# HMC5883L_Breakout-v14.net
KiCad netlist of a schematic drawn in EAGLE
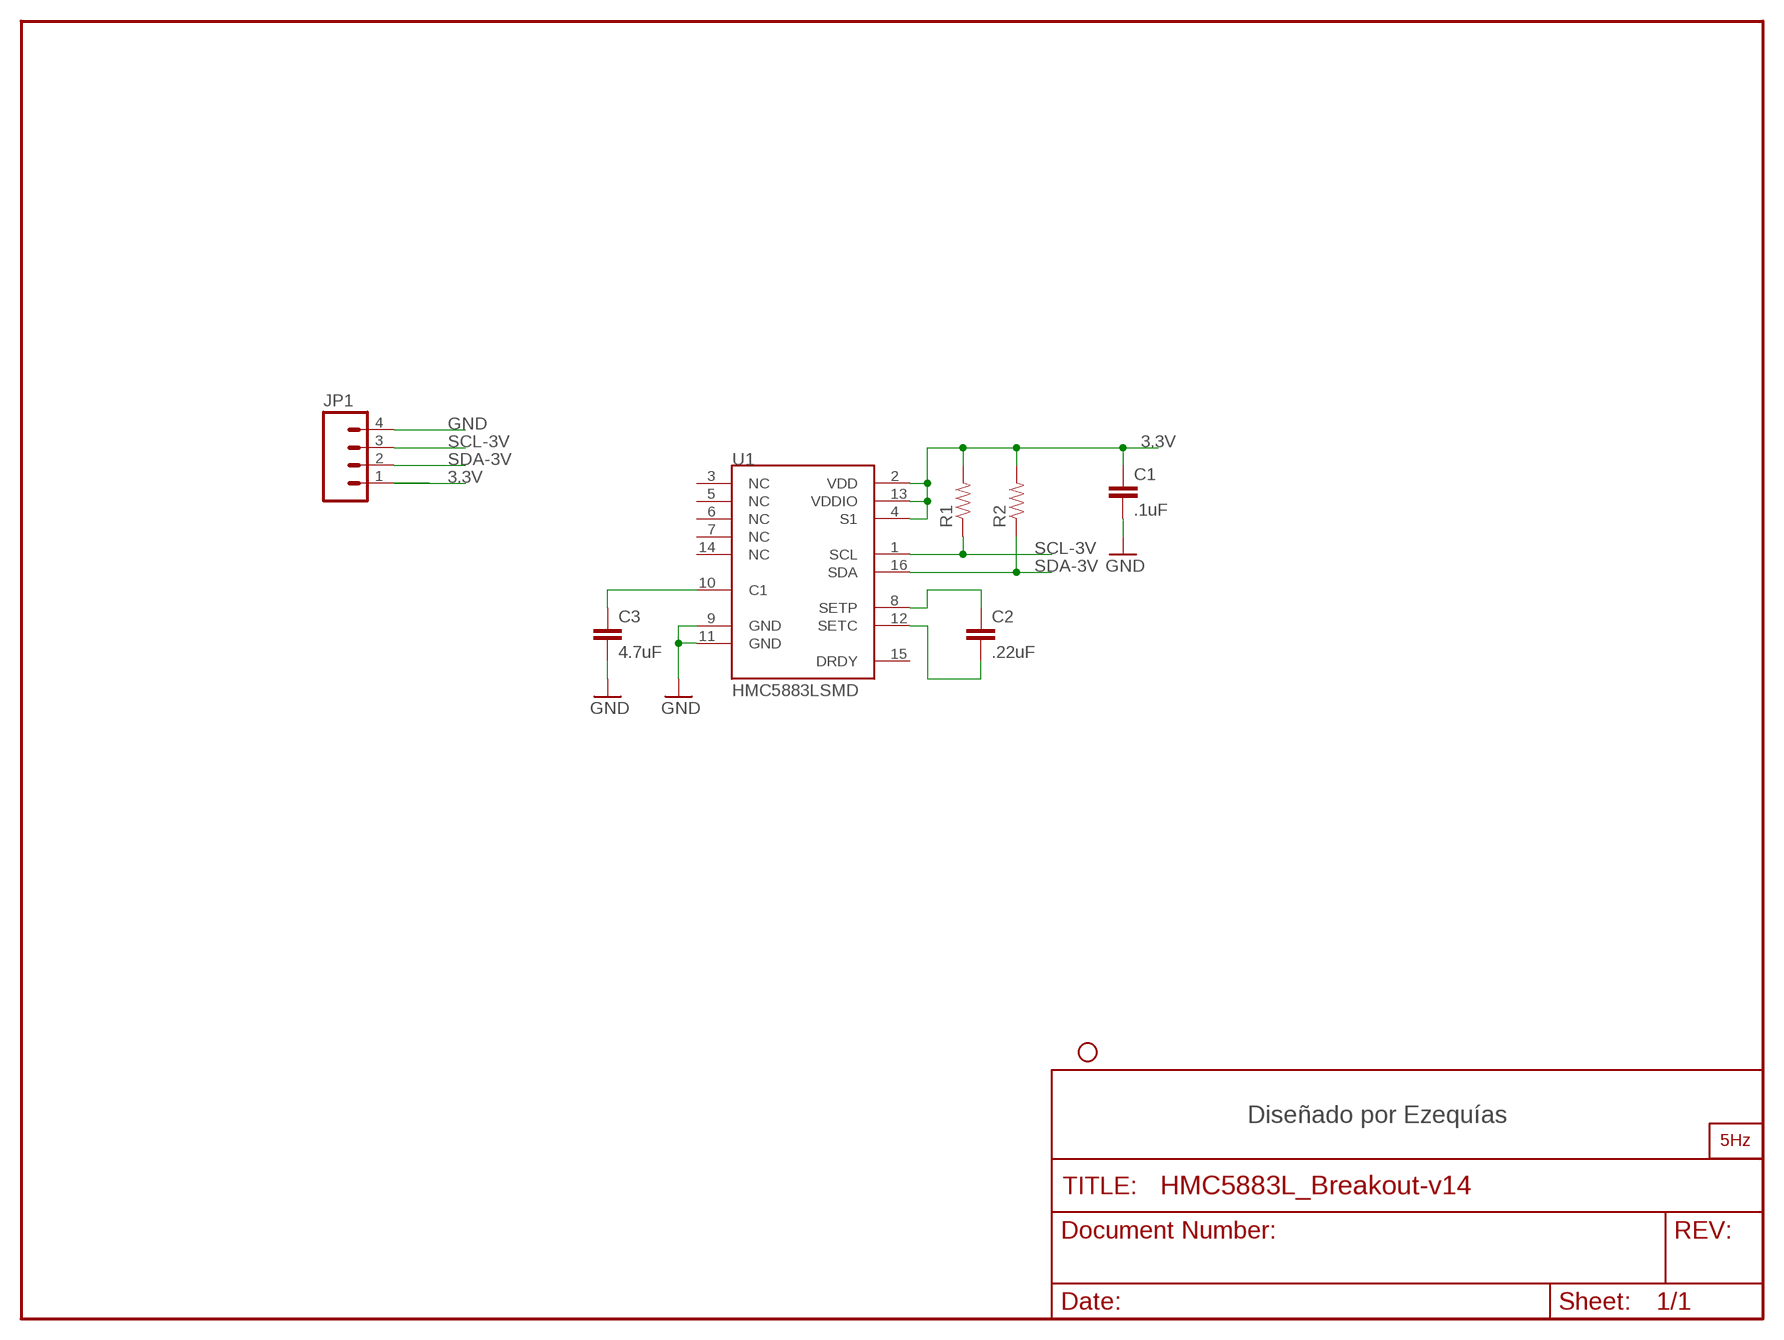
[diagram p0: schematic, sheet 1]

(export (version "E")
  (design (tool "Eeschema 10.0.6"))
  (components
    (comp (ref "C1")
      (value ".1uF")
      (footprint "eagle-import:0603-CAP")
      (libsource (lib "eagle-import") (part "CAP0603-CAP"))
    )
    (comp (ref "C2")
      (value ".22uF")
      (footprint "eagle-import:0603-CAP")
      (libsource (lib "eagle-import") (part "CAP0603-CAP"))
    )
    (comp (ref "C3")
      (value "4.7uF")
      (footprint "eagle-import:0603-CAP")
      (libsource (lib "eagle-import") (part "CAP0603-CAP"))
    )
    (comp (ref "JP1")
      (value "M04PTH")
      (footprint "eagle-import:1X04")
      (libsource (lib "eagle-import") (part "M04PTH"))
    )
    (comp (ref "JP4")
      (value "STAND-OFF")
      (footprint "eagle-import:STAND-OFF")
      (libsource (lib "eagle-import") (part "STAND-OFF"))
    )
    (comp (ref "R1")
      (value "RESISTORPTH-1/6W")
      (footprint "eagle-import:1_6W-RES")
      (libsource (lib "eagle-import") (part "RESISTORPTH-1/6W"))
    )
    (comp (ref "R2")
      (value "RESISTORPTH-1/6W")
      (footprint "eagle-import:1_6W-RES")
      (libsource (lib "eagle-import") (part "RESISTORPTH-1/6W"))
    )
    (comp (ref "U$1")
      (value "LOGO2_SILK5MM")
      (footprint "eagle-import:LOGO2_5MM")
      (libsource (lib "eagle-import") (part "LOGO2_SILK5MM"))
    )
    (comp (ref "U1")
      (value "HMC5883LSMD")
      (footprint "eagle-import:16LPCC")
      (libsource (lib "eagle-import") (part "HMC5883LSMD"))
    )
  )
  (nets
    (net (code "1") (name "/3.3V") (class "Default")
      (node (ref "C1") (pin "1") (pinfunction "1_1") (pintype "passive"))
      (node (ref "JP1") (pin "1") (pinfunction "1_1") (pintype "passive"))
      (node (ref "R1") (pin "2") (pinfunction "2_2") (pintype "passive"))
      (node (ref "R2") (pin "2") (pinfunction "2_2") (pintype "passive"))
      (node (ref "U1") (pin "13") (pinfunction "VDDIO_13") (pintype "bidirectional"))
      (node (ref "U1") (pin "2") (pinfunction "VDD_2") (pintype "bidirectional"))
      (node (ref "U1") (pin "4") (pinfunction "S1_4") (pintype "bidirectional"))
    )
    (net (code "2") (name "/SCL-3V") (class "Default")
      (node (ref "JP1") (pin "3") (pinfunction "3_3") (pintype "passive"))
      (node (ref "R1") (pin "1") (pinfunction "1_1") (pintype "passive"))
      (node (ref "U1") (pin "1") (pinfunction "SCL_1") (pintype "bidirectional"))
    )
    (net (code "3") (name "/SDA-3V") (class "Default")
      (node (ref "JP1") (pin "2") (pinfunction "2_2") (pintype "passive"))
      (node (ref "R2") (pin "1") (pinfunction "1_1") (pintype "passive"))
      (node (ref "U1") (pin "16") (pinfunction "SDA_16") (pintype "bidirectional"))
    )
    (net (code "4") (name "GND") (class "Default")
      (node (ref "C1") (pin "2") (pinfunction "2_2") (pintype "passive"))
      (node (ref "C3") (pin "2") (pinfunction "2_2") (pintype "passive"))
      (node (ref "JP1") (pin "4") (pinfunction "4_4") (pintype "passive"))
      (node (ref "U1") (pin "11") (pinfunction "GND_11") (pintype "bidirectional"))
      (node (ref "U1") (pin "9") (pinfunction "GND_9") (pintype "bidirectional"))
    )
    (net (code "5") (name "Net-(U1-C1)") (class "Default")
      (node (ref "C3") (pin "1") (pinfunction "1_1") (pintype "passive"))
      (node (ref "U1") (pin "10") (pinfunction "C1_10") (pintype "bidirectional"))
    )
    (net (code "6") (name "Net-(U1-SETC)") (class "Default")
      (node (ref "C2") (pin "2") (pinfunction "2_2") (pintype "passive"))
      (node (ref "U1") (pin "12") (pinfunction "SETC_12") (pintype "bidirectional"))
    )
    (net (code "7") (name "Net-(U1-SETP)") (class "Default")
      (node (ref "C2") (pin "1") (pinfunction "1_1") (pintype "passive"))
      (node (ref "U1") (pin "8") (pinfunction "SETP_8") (pintype "bidirectional"))
    )
    (net (code "8") (name "unconnected-(U1-DRDY-Pad15)") (class "Default")
      (node (ref "U1") (pin "15") (pinfunction "DRDY_15") (pintype "bidirectional"))
    )
    (net (code "9") (name "unconnected-(U1-NC-Pad3)") (class "Default")
      (node (ref "U1") (pin "3") (pinfunction "NC_3") (pintype "bidirectional"))
    )
    (net (code "10") (name "unconnected-(U1-NC-Pad5)") (class "Default")
      (node (ref "U1") (pin "5") (pinfunction "NC_5") (pintype "bidirectional"))
    )
    (net (code "11") (name "unconnected-(U1-NC-Pad6)") (class "Default")
      (node (ref "U1") (pin "6") (pinfunction "NC_6") (pintype "bidirectional"))
    )
    (net (code "12") (name "unconnected-(U1-NC-Pad7)") (class "Default")
      (node (ref "U1") (pin "7") (pinfunction "NC_7") (pintype "bidirectional"))
    )
    (net (code "13") (name "unconnected-(U1-NC-Pad14)") (class "Default")
      (node (ref "U1") (pin "14") (pinfunction "NC_14") (pintype "bidirectional"))
    )
  )
)
